# Headphone-Amplifier-ClassAB.net
KiCad netlist of a schematic drawn in EAGLE
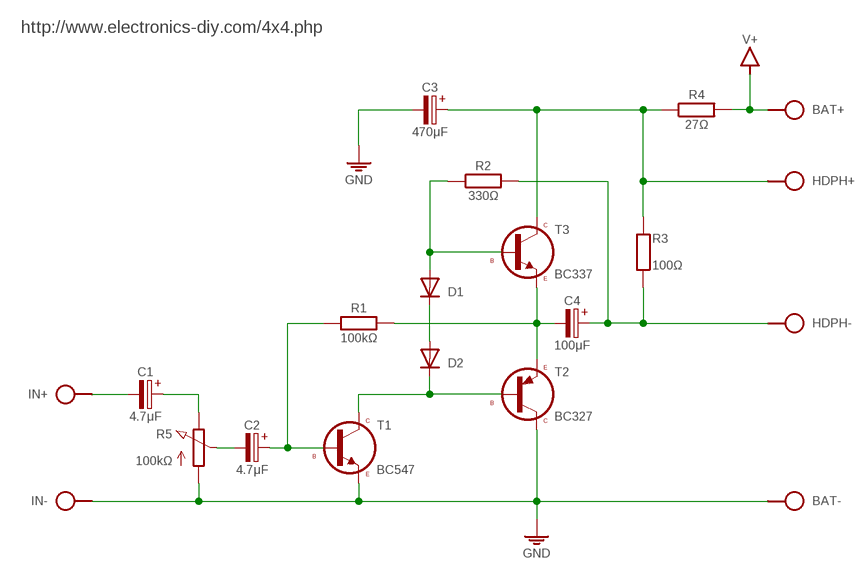
[diagram p0: schematic, sheet 1]

(export (version "E")
  (design (tool "Eeschema 10.0.6"))
  (components
    (comp (ref "BAT")
      (value "SPAD+-+-")
      (footprint "eagle-import:SPAD+-")
      (libsource (lib "eagle-import") (part "SPAD+-+-"))
    )
    (comp (ref "C1")
      (value "4.7μF")
      (footprint "eagle-import:E2,5-4")
      (libsource (lib "eagle-import") (part "CPOLE2,5-4"))
    )
    (comp (ref "C2")
      (value "4.7μF")
      (footprint "eagle-import:E2,5-4")
      (libsource (lib "eagle-import") (part "CPOLE2,5-4"))
    )
    (comp (ref "C3")
      (value "470μF")
      (footprint "eagle-import:E5-6")
      (libsource (lib "eagle-import") (part "CPOLE5-6"))
    )
    (comp (ref "C4")
      (value "100μF")
      (footprint "eagle-import:E5-4")
      (libsource (lib "eagle-import") (part "CPOLE5-4"))
    )
    (comp (ref "D1")
      (value "1N414834-5V")
      (footprint "eagle-import:DO34-5V")
      (libsource (lib "eagle-import") (part "1N414834-5V"))
    )
    (comp (ref "D2")
      (value "1N414834-5V")
      (footprint "eagle-import:DO34-5V")
      (libsource (lib "eagle-import") (part "1N414834-5V"))
    )
    (comp (ref "HDPH")
      (value "SPAD+--+")
      (footprint "eagle-import:SPAD-+")
      (libsource (lib "eagle-import") (part "SPAD+--+"))
    )
    (comp (ref "IN")
      (value "SPAD+--+")
      (footprint "eagle-import:SPAD-+")
      (libsource (lib "eagle-import") (part "SPAD+--+"))
    )
    (comp (ref "R1")
      (value "100kΩ")
      (footprint "eagle-import:0202_7")
      (libsource (lib "eagle-import") (part "R-H0202/7"))
    )
    (comp (ref "R2")
      (value "330Ω")
      (footprint "eagle-import:0204_10")
      (libsource (lib "eagle-import") (part "R-H0204/10"))
    )
    (comp (ref "R3")
      (value "100Ω")
      (footprint "eagle-import:0204_10")
      (libsource (lib "eagle-import") (part "R0204/10"))
    )
    (comp (ref "R4")
      (value "27Ω")
      (footprint "eagle-import:0204V")
      (libsource (lib "eagle-import") (part "R-H-V-X"))
    )
    (comp (ref "R5")
      (value "100kΩ")
      (footprint "eagle-import:CONN-3P")
      (libsource (lib "eagle-import") (part "POT-3P"))
    )
    (comp (ref "T1")
      (value "BC547")
      (footprint "eagle-import:TO92")
      (libsource (lib "eagle-import") (part "BC547"))
    )
    (comp (ref "T2")
      (value "BC327")
      (footprint "eagle-import:TO92")
      (libsource (lib "eagle-import") (part "BC327"))
    )
    (comp (ref "T3")
      (value "BC337")
      (footprint "eagle-import:TO92-CBE")
      (libsource (lib "eagle-import") (part "BC337CBE"))
    )
  )
  (nets
    (net (code "1") (name "GND") (class "Default")
      (node (ref "BAT") (pin "1") (pinfunction "P$1_1") (pintype "passive"))
      (node (ref "C3") (pin "-") (pinfunction "-_-") (pintype "passive"))
      (node (ref "IN") (pin "1") (pinfunction "P$1_1") (pintype "passive"))
      (node (ref "R5") (pin "1") (pinfunction "A_1") (pintype "passive"))
      (node (ref "T1") (pin "3") (pinfunction "E_3") (pintype "passive"))
      (node (ref "T2") (pin "1") (pinfunction "C_1") (pintype "passive"))
    )
    (net (code "2") (name "Net-(D1-PadC)") (class "Default")
      (node (ref "D1") (pin "C") (pinfunction "C_C") (pintype "passive"))
      (node (ref "D2") (pin "A") (pinfunction "A_A") (pintype "passive"))
    )
    (net (code "3") (name "Net-(HDPHA-P$1)") (class "Default")
      (node (ref "C3") (pin "+") (pinfunction "+_+") (pintype "passive"))
      (node (ref "HDPH") (pin "2") (pinfunction "P$1_2") (pintype "passive"))
      (node (ref "R3") (pin "2") (pinfunction "1_2") (pintype "passive"))
      (node (ref "R4") (pin "2") (pinfunction "1_2") (pintype "passive"))
      (node (ref "T3") (pin "1") (pinfunction "C_1") (pintype "passive"))
    )
    (net (code "4") (name "Net-(HDPHB-P$1)") (class "Default")
      (node (ref "C4") (pin "+") (pinfunction "+_+") (pintype "passive"))
      (node (ref "HDPH") (pin "1") (pinfunction "P$1_1") (pintype "passive"))
      (node (ref "R2") (pin "2") (pinfunction "2_2") (pintype "passive"))
      (node (ref "R3") (pin "1") (pinfunction "2_1") (pintype "passive"))
    )
    (net (code "5") (name "Net-(INA-P$1)") (class "Default")
      (node (ref "C1") (pin "-") (pinfunction "-_-") (pintype "passive"))
      (node (ref "IN") (pin "2") (pinfunction "P$1_2") (pintype "passive"))
    )
    (net (code "6") (name "Net-(R5-E)") (class "Default")
      (node (ref "C1") (pin "+") (pinfunction "+_+") (pintype "passive"))
      (node (ref "R5") (pin "3") (pinfunction "E_3") (pintype "passive"))
    )
    (net (code "7") (name "Net-(R5-S)") (class "Default")
      (node (ref "C2") (pin "-") (pinfunction "-_-") (pintype "passive"))
      (node (ref "R5") (pin "2") (pinfunction "S_2") (pintype "passive"))
    )
    (net (code "8") (name "Net-(T1-B)") (class "Default")
      (node (ref "C2") (pin "+") (pinfunction "+_+") (pintype "passive"))
      (node (ref "R1") (pin "1") (pinfunction "1_1") (pintype "passive"))
      (node (ref "T1") (pin "2") (pinfunction "B_2") (pintype "passive"))
    )
    (net (code "9") (name "Net-(T1-C)") (class "Default")
      (node (ref "D2") (pin "C") (pinfunction "C_C") (pintype "passive"))
      (node (ref "T1") (pin "1") (pinfunction "C_1") (pintype "passive"))
      (node (ref "T2") (pin "2") (pinfunction "B_2") (pintype "passive"))
    )
    (net (code "10") (name "Net-(T2-E)") (class "Default")
      (node (ref "C4") (pin "-") (pinfunction "-_-") (pintype "passive"))
      (node (ref "R1") (pin "2") (pinfunction "2_2") (pintype "passive"))
      (node (ref "T2") (pin "3") (pinfunction "E_3") (pintype "passive"))
      (node (ref "T3") (pin "3") (pinfunction "E_3") (pintype "passive"))
    )
    (net (code "11") (name "Net-(T3-B)") (class "Default")
      (node (ref "D1") (pin "A") (pinfunction "A_A") (pintype "passive"))
      (node (ref "R2") (pin "1") (pinfunction "1_1") (pintype "passive"))
      (node (ref "T3") (pin "2") (pinfunction "B_2") (pintype "passive"))
    )
    (net (code "12") (name "V+") (class "Default")
      (node (ref "BAT") (pin "2") (pinfunction "P$1_2") (pintype "passive"))
      (node (ref "R4") (pin "1") (pinfunction "2_1") (pintype "passive"))
    )
  )
)
